# HuXtension_rev_A_layer1.net
KiCad netlist of a schematic drawn in EAGLE
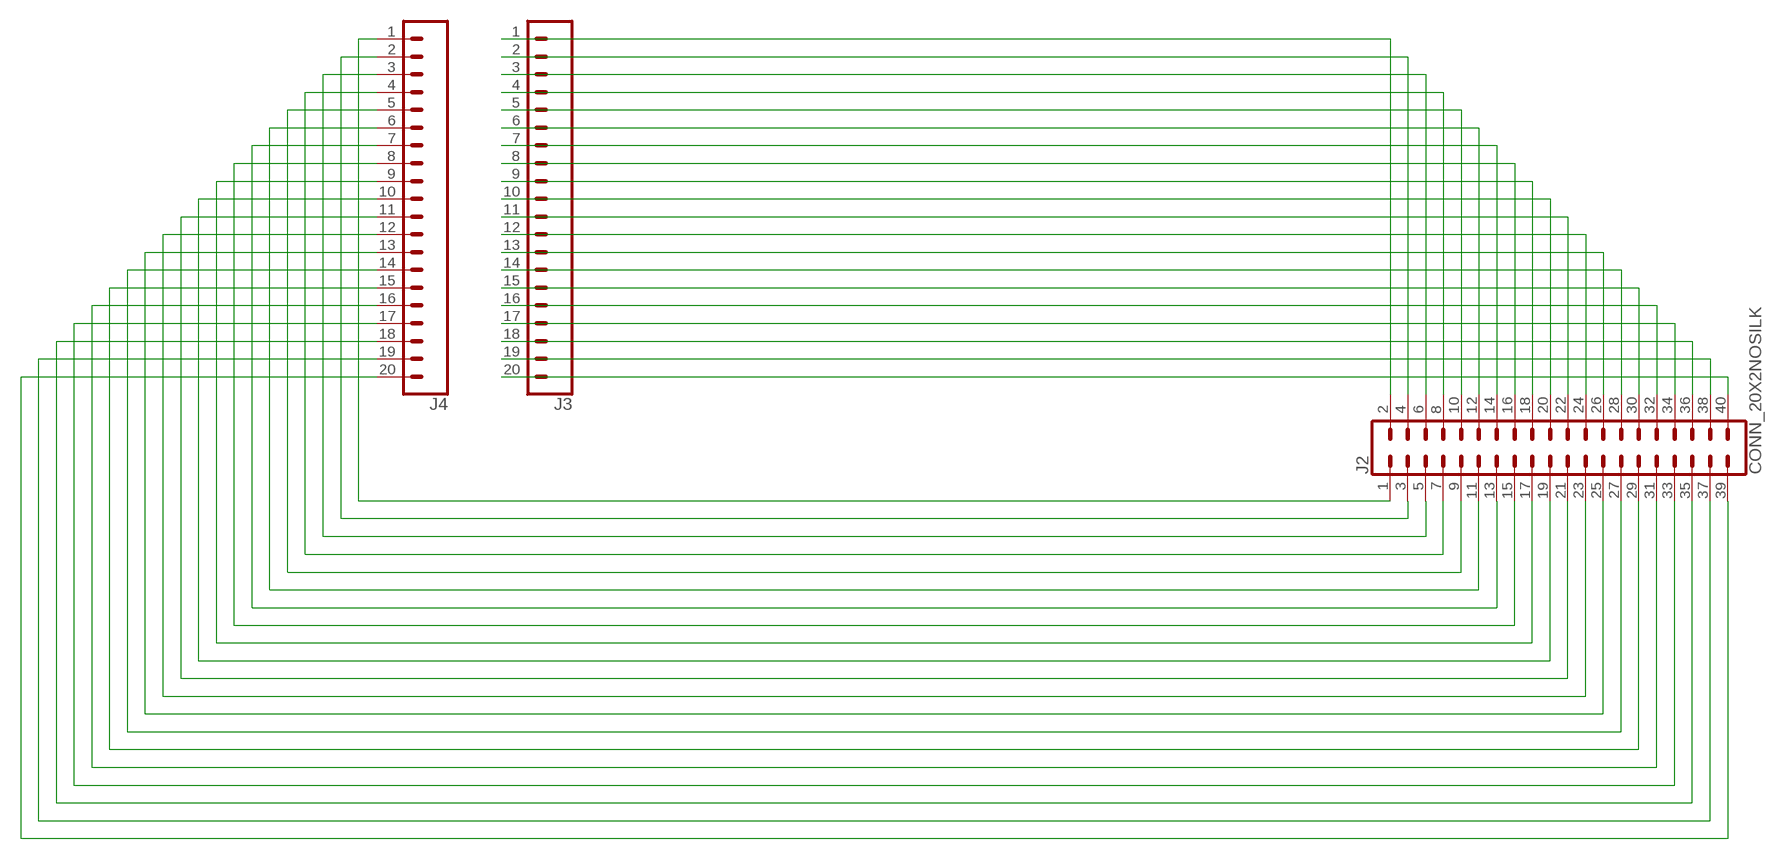
[diagram p0: schematic, sheet 1]

(export (version "E")
  (design (tool "Eeschema 10.0.6"))
  (components
    (comp (ref "J2")
      (value "CONN_20X2NOSILK")
      (footprint "eagle-import:2X20_NOSILK")
      (libsource (lib "eagle-import") (part "CONN_20X2NOSILK"))
    )
    (comp (ref "J3")
      (value "CONN_20NOSILK")
      (footprint "eagle-import:1X20_NOSILK")
      (libsource (lib "eagle-import") (part "CONN_20NOSILK"))
    )
    (comp (ref "J4")
      (value "CONN_20NOSILK")
      (footprint "eagle-import:1X20_NOSILK")
      (libsource (lib "eagle-import") (part "CONN_20NOSILK"))
    )
  )
  (nets
    (net (code "1") (name "Net-(J2-Pad1)") (class "Default")
      (node (ref "J2") (pin "1") (pinfunction "1_1") (pintype "passive"))
      (node (ref "J4") (pin "1") (pinfunction "1_1") (pintype "passive"))
    )
    (net (code "2") (name "Net-(J2-Pad2)") (class "Default")
      (node (ref "J2") (pin "2") (pinfunction "2_2") (pintype "passive"))
      (node (ref "J3") (pin "1") (pinfunction "1_1") (pintype "passive"))
    )
    (net (code "3") (name "Net-(J2-Pad3)") (class "Default")
      (node (ref "J2") (pin "3") (pinfunction "3_3") (pintype "passive"))
      (node (ref "J4") (pin "2") (pinfunction "2_2") (pintype "passive"))
    )
    (net (code "4") (name "Net-(J2-Pad4)") (class "Default")
      (node (ref "J2") (pin "4") (pinfunction "4_4") (pintype "passive"))
      (node (ref "J3") (pin "2") (pinfunction "2_2") (pintype "passive"))
    )
    (net (code "5") (name "Net-(J2-Pad5)") (class "Default")
      (node (ref "J2") (pin "5") (pinfunction "5_5") (pintype "passive"))
      (node (ref "J4") (pin "3") (pinfunction "3_3") (pintype "passive"))
    )
    (net (code "6") (name "Net-(J2-Pad6)") (class "Default")
      (node (ref "J2") (pin "6") (pinfunction "6_6") (pintype "passive"))
      (node (ref "J3") (pin "3") (pinfunction "3_3") (pintype "passive"))
    )
    (net (code "7") (name "Net-(J2-Pad7)") (class "Default")
      (node (ref "J2") (pin "7") (pinfunction "7_7") (pintype "passive"))
      (node (ref "J4") (pin "4") (pinfunction "4_4") (pintype "passive"))
    )
    (net (code "8") (name "Net-(J2-Pad8)") (class "Default")
      (node (ref "J2") (pin "8") (pinfunction "8_8") (pintype "passive"))
      (node (ref "J3") (pin "4") (pinfunction "4_4") (pintype "passive"))
    )
    (net (code "9") (name "Net-(J2-Pad9)") (class "Default")
      (node (ref "J2") (pin "9") (pinfunction "9_9") (pintype "passive"))
      (node (ref "J4") (pin "5") (pinfunction "5_5") (pintype "passive"))
    )
    (net (code "10") (name "Net-(J2-Pad10)") (class "Default")
      (node (ref "J2") (pin "10") (pinfunction "10_10") (pintype "passive"))
      (node (ref "J3") (pin "5") (pinfunction "5_5") (pintype "passive"))
    )
    (net (code "11") (name "Net-(J2-Pad11)") (class "Default")
      (node (ref "J2") (pin "11") (pinfunction "11_11") (pintype "passive"))
      (node (ref "J4") (pin "6") (pinfunction "6_6") (pintype "passive"))
    )
    (net (code "12") (name "Net-(J2-Pad12)") (class "Default")
      (node (ref "J2") (pin "12") (pinfunction "12_12") (pintype "passive"))
      (node (ref "J3") (pin "6") (pinfunction "6_6") (pintype "passive"))
    )
    (net (code "13") (name "Net-(J2-Pad13)") (class "Default")
      (node (ref "J2") (pin "13") (pinfunction "13_13") (pintype "passive"))
      (node (ref "J4") (pin "7") (pinfunction "7_7") (pintype "passive"))
    )
    (net (code "14") (name "Net-(J2-Pad14)") (class "Default")
      (node (ref "J2") (pin "14") (pinfunction "14_14") (pintype "passive"))
      (node (ref "J3") (pin "7") (pinfunction "7_7") (pintype "passive"))
    )
    (net (code "15") (name "Net-(J2-Pad15)") (class "Default")
      (node (ref "J2") (pin "15") (pinfunction "15_15") (pintype "passive"))
      (node (ref "J4") (pin "8") (pinfunction "8_8") (pintype "passive"))
    )
    (net (code "16") (name "Net-(J2-Pad16)") (class "Default")
      (node (ref "J2") (pin "16") (pinfunction "16_16") (pintype "passive"))
      (node (ref "J3") (pin "8") (pinfunction "8_8") (pintype "passive"))
    )
    (net (code "17") (name "Net-(J2-Pad17)") (class "Default")
      (node (ref "J2") (pin "17") (pinfunction "17_17") (pintype "passive"))
      (node (ref "J4") (pin "9") (pinfunction "9_9") (pintype "passive"))
    )
    (net (code "18") (name "Net-(J2-Pad18)") (class "Default")
      (node (ref "J2") (pin "18") (pinfunction "18_18") (pintype "passive"))
      (node (ref "J3") (pin "9") (pinfunction "9_9") (pintype "passive"))
    )
    (net (code "19") (name "Net-(J2-Pad19)") (class "Default")
      (node (ref "J2") (pin "19") (pinfunction "19_19") (pintype "passive"))
      (node (ref "J4") (pin "10") (pinfunction "10_10") (pintype "passive"))
    )
    (net (code "20") (name "Net-(J2-Pad20)") (class "Default")
      (node (ref "J2") (pin "20") (pinfunction "20_20") (pintype "passive"))
      (node (ref "J3") (pin "10") (pinfunction "10_10") (pintype "passive"))
    )
    (net (code "21") (name "Net-(J2-Pad21)") (class "Default")
      (node (ref "J2") (pin "21") (pinfunction "21_21") (pintype "passive"))
      (node (ref "J4") (pin "11") (pinfunction "11_11") (pintype "passive"))
    )
    (net (code "22") (name "Net-(J2-Pad22)") (class "Default")
      (node (ref "J2") (pin "22") (pinfunction "22_22") (pintype "passive"))
      (node (ref "J3") (pin "11") (pinfunction "11_11") (pintype "passive"))
    )
    (net (code "23") (name "Net-(J2-Pad23)") (class "Default")
      (node (ref "J2") (pin "23") (pinfunction "23_23") (pintype "passive"))
      (node (ref "J4") (pin "12") (pinfunction "12_12") (pintype "passive"))
    )
    (net (code "24") (name "Net-(J2-Pad24)") (class "Default")
      (node (ref "J2") (pin "24") (pinfunction "24_24") (pintype "passive"))
      (node (ref "J3") (pin "12") (pinfunction "12_12") (pintype "passive"))
    )
    (net (code "25") (name "Net-(J2-Pad25)") (class "Default")
      (node (ref "J2") (pin "25") (pinfunction "25_25") (pintype "passive"))
      (node (ref "J4") (pin "13") (pinfunction "13_13") (pintype "passive"))
    )
    (net (code "26") (name "Net-(J2-Pad26)") (class "Default")
      (node (ref "J2") (pin "26") (pinfunction "26_26") (pintype "passive"))
      (node (ref "J3") (pin "13") (pinfunction "13_13") (pintype "passive"))
    )
    (net (code "27") (name "Net-(J2-Pad27)") (class "Default")
      (node (ref "J2") (pin "27") (pinfunction "27_27") (pintype "passive"))
      (node (ref "J4") (pin "14") (pinfunction "14_14") (pintype "passive"))
    )
    (net (code "28") (name "Net-(J2-Pad28)") (class "Default")
      (node (ref "J2") (pin "28") (pinfunction "28_28") (pintype "passive"))
      (node (ref "J3") (pin "14") (pinfunction "14_14") (pintype "passive"))
    )
    (net (code "29") (name "Net-(J2-Pad29)") (class "Default")
      (node (ref "J2") (pin "29") (pinfunction "29_29") (pintype "passive"))
      (node (ref "J4") (pin "15") (pinfunction "15_15") (pintype "passive"))
    )
    (net (code "30") (name "Net-(J2-Pad30)") (class "Default")
      (node (ref "J2") (pin "30") (pinfunction "30_30") (pintype "passive"))
      (node (ref "J3") (pin "15") (pinfunction "15_15") (pintype "passive"))
    )
    (net (code "31") (name "Net-(J2-Pad31)") (class "Default")
      (node (ref "J2") (pin "31") (pinfunction "31_31") (pintype "passive"))
      (node (ref "J4") (pin "16") (pinfunction "16_16") (pintype "passive"))
    )
    (net (code "32") (name "Net-(J2-Pad32)") (class "Default")
      (node (ref "J2") (pin "32") (pinfunction "32_32") (pintype "passive"))
      (node (ref "J3") (pin "16") (pinfunction "16_16") (pintype "passive"))
    )
    (net (code "33") (name "Net-(J2-Pad33)") (class "Default")
      (node (ref "J2") (pin "33") (pinfunction "33_33") (pintype "passive"))
      (node (ref "J4") (pin "17") (pinfunction "17_17") (pintype "passive"))
    )
    (net (code "34") (name "Net-(J2-Pad34)") (class "Default")
      (node (ref "J2") (pin "34") (pinfunction "34_34") (pintype "passive"))
      (node (ref "J3") (pin "17") (pinfunction "17_17") (pintype "passive"))
    )
    (net (code "35") (name "Net-(J2-Pad35)") (class "Default")
      (node (ref "J2") (pin "35") (pinfunction "35_35") (pintype "passive"))
      (node (ref "J4") (pin "18") (pinfunction "18_18") (pintype "passive"))
    )
    (net (code "36") (name "Net-(J2-Pad36)") (class "Default")
      (node (ref "J2") (pin "36") (pinfunction "36_36") (pintype "passive"))
      (node (ref "J3") (pin "18") (pinfunction "18_18") (pintype "passive"))
    )
    (net (code "37") (name "Net-(J2-Pad37)") (class "Default")
      (node (ref "J2") (pin "37") (pinfunction "37_37") (pintype "passive"))
      (node (ref "J4") (pin "19") (pinfunction "19_19") (pintype "passive"))
    )
    (net (code "38") (name "Net-(J2-Pad38)") (class "Default")
      (node (ref "J2") (pin "38") (pinfunction "38_38") (pintype "passive"))
      (node (ref "J3") (pin "19") (pinfunction "19_19") (pintype "passive"))
    )
    (net (code "39") (name "Net-(J2-Pad39)") (class "Default")
      (node (ref "J2") (pin "39") (pinfunction "39_39") (pintype "passive"))
      (node (ref "J4") (pin "20") (pinfunction "20_20") (pintype "passive"))
    )
    (net (code "40") (name "Net-(J2-Pad40)") (class "Default")
      (node (ref "J2") (pin "40") (pinfunction "40_40") (pintype "passive"))
      (node (ref "J3") (pin "20") (pinfunction "20_20") (pintype "passive"))
    )
  )
)
